# mixer-board1.net
KiCad netlist of a schematic drawn in EAGLE
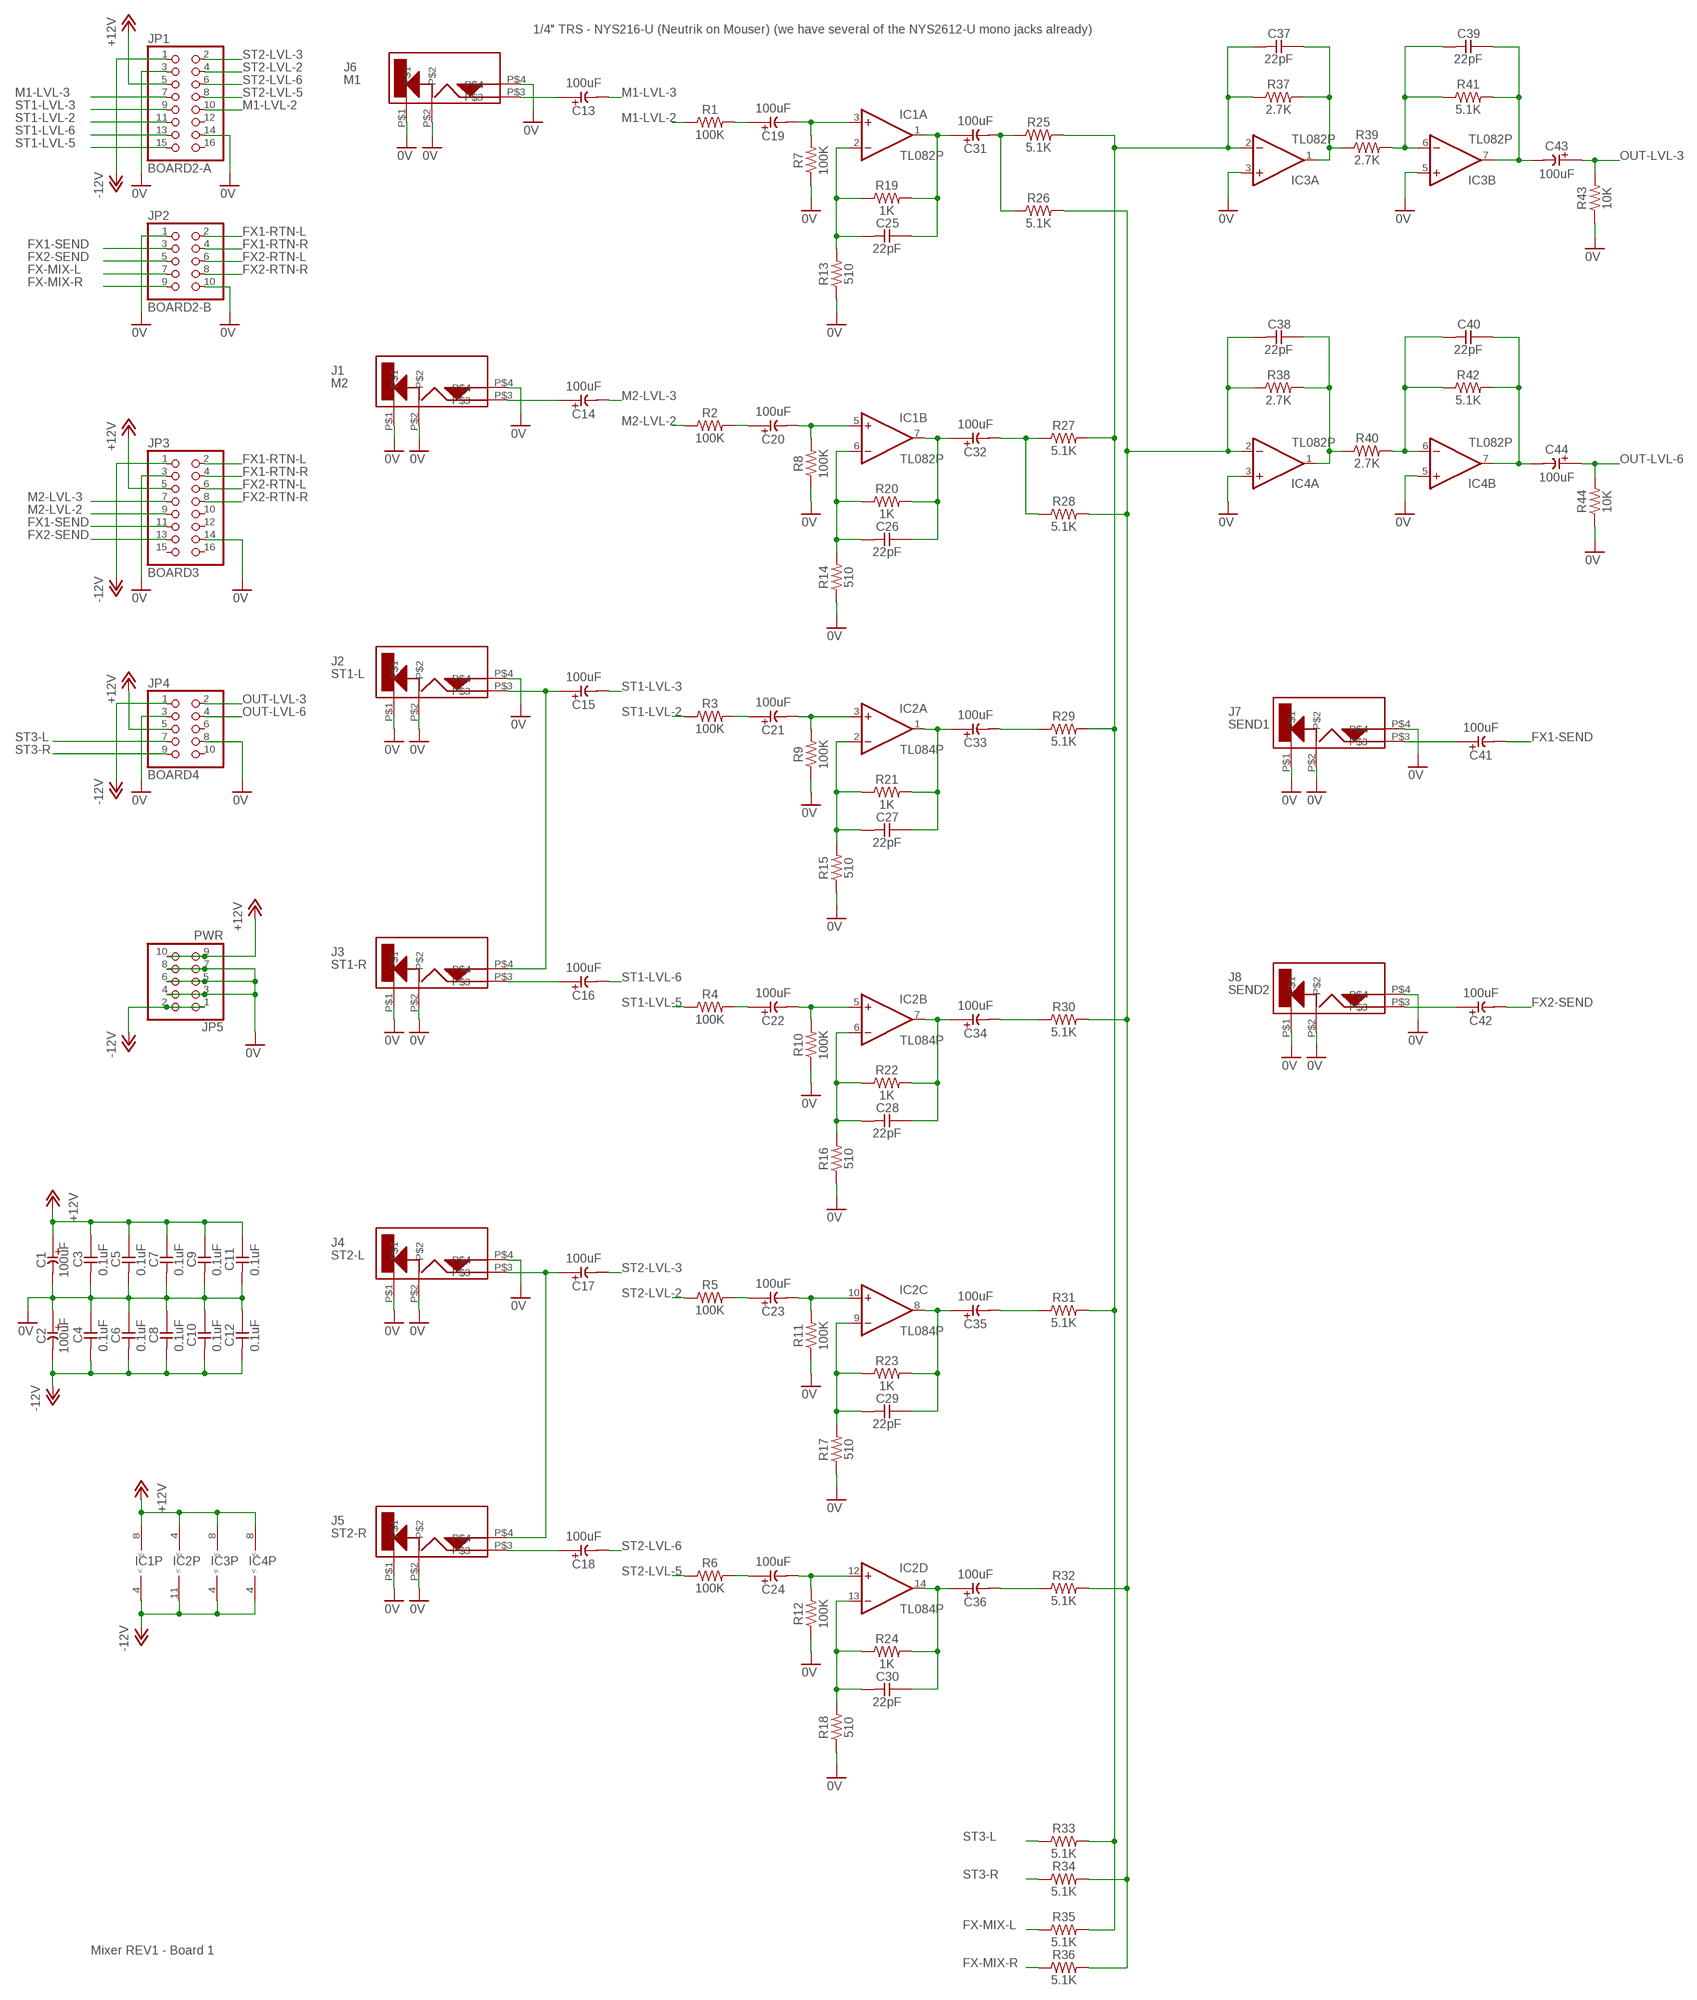
[diagram p0: schematic, sheet 1]

(export (version "E")
  (design (tool "Eeschema 10.0.6"))
  (components
    (comp (ref "C1")
      (value "100uF")
      (footprint "eagle-import:E5-8,5")
      (libsource (lib "eagle-import") (part "CE-USE5-8.5"))
    )
    (comp (ref "C2")
      (value "100uF")
      (footprint "eagle-import:E5-8,5")
      (libsource (lib "eagle-import") (part "CE-USE5-8.5"))
    )
    (comp (ref "C3")
      (value "0.1uF")
      (footprint "eagle-import:C025-024X044")
      (libsource (lib "eagle-import") (part "_common.v1_CC-US025-024X044"))
    )
    (comp (ref "C4")
      (value "0.1uF")
      (footprint "eagle-import:C025-024X044")
      (libsource (lib "eagle-import") (part "_common.v1_CC-US025-024X044"))
    )
    (comp (ref "C5")
      (value "0.1uF")
      (footprint "eagle-import:C025-024X044")
      (libsource (lib "eagle-import") (part "_common.v1_CC-US025-024X044"))
    )
    (comp (ref "C6")
      (value "0.1uF")
      (footprint "eagle-import:C025-024X044")
      (libsource (lib "eagle-import") (part "_common.v1_CC-US025-024X044"))
    )
    (comp (ref "C7")
      (value "0.1uF")
      (footprint "eagle-import:C025-024X044")
      (libsource (lib "eagle-import") (part "_common.v1_CC-US025-024X044"))
    )
    (comp (ref "C8")
      (value "0.1uF")
      (footprint "eagle-import:C025-024X044")
      (libsource (lib "eagle-import") (part "_common.v1_CC-US025-024X044"))
    )
    (comp (ref "C9")
      (value "0.1uF")
      (footprint "eagle-import:C025-024X044")
      (libsource (lib "eagle-import") (part "_common.v1_CC-US025-024X044"))
    )
    (comp (ref "C10")
      (value "0.1uF")
      (footprint "eagle-import:C025-024X044")
      (libsource (lib "eagle-import") (part "_common.v1_CC-US025-024X044"))
    )
    (comp (ref "C11")
      (value "0.1uF")
      (footprint "eagle-import:C025-024X044")
      (libsource (lib "eagle-import") (part "_common.v1_CC-US025-024X044"))
    )
    (comp (ref "C12")
      (value "0.1uF")
      (footprint "eagle-import:C025-024X044")
      (libsource (lib "eagle-import") (part "_common.v1_CC-US025-024X044"))
    )
    (comp (ref "C13")
      (value "100uF")
      (footprint "eagle-import:E5-8,5")
      (libsource (lib "eagle-import") (part "CE-USE5-8.5"))
    )
    (comp (ref "C14")
      (value "100uF")
      (footprint "eagle-import:E5-8,5")
      (libsource (lib "eagle-import") (part "CE-USE5-8.5"))
    )
    (comp (ref "C15")
      (value "100uF")
      (footprint "eagle-import:E5-8,5")
      (libsource (lib "eagle-import") (part "CE-USE5-8.5"))
    )
    (comp (ref "C16")
      (value "100uF")
      (footprint "eagle-import:E5-8,5")
      (libsource (lib "eagle-import") (part "CE-USE5-8.5"))
    )
    (comp (ref "C17")
      (value "100uF")
      (footprint "eagle-import:E5-8,5")
      (libsource (lib "eagle-import") (part "CE-USE5-8.5"))
    )
    (comp (ref "C18")
      (value "100uF")
      (footprint "eagle-import:E5-8,5")
      (libsource (lib "eagle-import") (part "CE-USE5-8.5"))
    )
    (comp (ref "C19")
      (value "100uF")
      (footprint "eagle-import:E5-8,5")
      (libsource (lib "eagle-import") (part "CE-USE5-8.5"))
    )
    (comp (ref "C20")
      (value "100uF")
      (footprint "eagle-import:E5-8,5")
      (libsource (lib "eagle-import") (part "CE-USE5-8.5"))
    )
    (comp (ref "C21")
      (value "100uF")
      (footprint "eagle-import:E5-8,5")
      (libsource (lib "eagle-import") (part "CE-USE5-8.5"))
    )
    (comp (ref "C22")
      (value "100uF")
      (footprint "eagle-import:E5-8,5")
      (libsource (lib "eagle-import") (part "CE-USE5-8.5"))
    )
    (comp (ref "C23")
      (value "100uF")
      (footprint "eagle-import:E5-8,5")
      (libsource (lib "eagle-import") (part "CE-USE5-8.5"))
    )
    (comp (ref "C24")
      (value "100uF")
      (footprint "eagle-import:E5-8,5")
      (libsource (lib "eagle-import") (part "CE-USE5-8.5"))
    )
    (comp (ref "C25")
      (value "22pF")
      (footprint "eagle-import:C025-024X044")
      (libsource (lib "eagle-import") (part "CC-US025-024X044"))
    )
    (comp (ref "C26")
      (value "22pF")
      (footprint "eagle-import:C025-024X044")
      (libsource (lib "eagle-import") (part "CC-US025-024X044"))
    )
    (comp (ref "C27")
      (value "22pF")
      (footprint "eagle-import:C025-024X044")
      (libsource (lib "eagle-import") (part "CC-US025-024X044"))
    )
    (comp (ref "C28")
      (value "22pF")
      (footprint "eagle-import:C025-024X044")
      (libsource (lib "eagle-import") (part "CC-US025-024X044"))
    )
    (comp (ref "C29")
      (value "22pF")
      (footprint "eagle-import:C025-024X044")
      (libsource (lib "eagle-import") (part "CC-US025-024X044"))
    )
    (comp (ref "C30")
      (value "22pF")
      (footprint "eagle-import:C025-024X044")
      (libsource (lib "eagle-import") (part "CC-US025-024X044"))
    )
    (comp (ref "C31")
      (value "100uF")
      (footprint "eagle-import:E5-8,5")
      (libsource (lib "eagle-import") (part "CE-USE5-8.5"))
    )
    (comp (ref "C32")
      (value "100uF")
      (footprint "eagle-import:E5-8,5")
      (libsource (lib "eagle-import") (part "CE-USE5-8.5"))
    )
    (comp (ref "C33")
      (value "100uF")
      (footprint "eagle-import:E5-8,5")
      (libsource (lib "eagle-import") (part "CE-USE5-8.5"))
    )
    (comp (ref "C34")
      (value "100uF")
      (footprint "eagle-import:E5-8,5")
      (libsource (lib "eagle-import") (part "CE-USE5-8.5"))
    )
    (comp (ref "C35")
      (value "100uF")
      (footprint "eagle-import:E5-8,5")
      (libsource (lib "eagle-import") (part "CE-USE5-8.5"))
    )
    (comp (ref "C36")
      (value "100uF")
      (footprint "eagle-import:E5-8,5")
      (libsource (lib "eagle-import") (part "CE-USE5-8.5"))
    )
    (comp (ref "C37")
      (value "22pF")
      (footprint "eagle-import:C025-024X044")
      (libsource (lib "eagle-import") (part "CC-US025-024X044"))
    )
    (comp (ref "C38")
      (value "22pF")
      (footprint "eagle-import:C025-024X044")
      (libsource (lib "eagle-import") (part "CC-US025-024X044"))
    )
    (comp (ref "C39")
      (value "22pF")
      (footprint "eagle-import:C025-024X044")
      (libsource (lib "eagle-import") (part "CC-US025-024X044"))
    )
    (comp (ref "C40")
      (value "22pF")
      (footprint "eagle-import:C025-024X044")
      (libsource (lib "eagle-import") (part "CC-US025-024X044"))
    )
    (comp (ref "C41")
      (value "100uF")
      (footprint "eagle-import:E5-8,5")
      (libsource (lib "eagle-import") (part "CE-USE5-8.5"))
    )
    (comp (ref "C42")
      (value "100uF")
      (footprint "eagle-import:E5-8,5")
      (libsource (lib "eagle-import") (part "CE-USE5-8.5"))
    )
    (comp (ref "C43")
      (value "100uF")
      (footprint "eagle-import:E5-8,5")
      (libsource (lib "eagle-import") (part "CE-USE5-8.5"))
    )
    (comp (ref "C44")
      (value "100uF")
      (footprint "eagle-import:E5-8,5")
      (libsource (lib "eagle-import") (part "CE-USE5-8.5"))
    )
    (comp (ref "IC1")
      (value "TL082P")
      (footprint "eagle-import:DIL08")
      (libsource (lib "eagle-import") (part "TL082P"))
    )
    (comp (ref "IC2")
      (value "TL084P")
      (footprint "eagle-import:DIL14")
      (libsource (lib "eagle-import") (part "TL084P"))
    )
    (comp (ref "IC3")
      (value "TL082P")
      (footprint "eagle-import:DIL08")
      (libsource (lib "eagle-import") (part "TL082P"))
    )
    (comp (ref "IC4")
      (value "TL082P")
      (footprint "eagle-import:DIL08")
      (libsource (lib "eagle-import") (part "TL082P"))
    )
    (comp (ref "J1")
      (value "M2")
      (footprint "eagle-import:CL1384")
      (libsource (lib "eagle-import") (part "CL1384"))
    )
    (comp (ref "J2")
      (value "ST1-L")
      (footprint "eagle-import:CL1384")
      (libsource (lib "eagle-import") (part "CL1384"))
    )
    (comp (ref "J3")
      (value "ST1-R")
      (footprint "eagle-import:CL1384")
      (libsource (lib "eagle-import") (part "CL1384"))
    )
    (comp (ref "J4")
      (value "ST2-L")
      (footprint "eagle-import:CL1384")
      (libsource (lib "eagle-import") (part "CL1384"))
    )
    (comp (ref "J5")
      (value "ST2-R")
      (footprint "eagle-import:CL1384")
      (libsource (lib "eagle-import") (part "CL1384"))
    )
    (comp (ref "J6")
      (value "M1")
      (footprint "eagle-import:CL1384")
      (libsource (lib "eagle-import") (part "CL1384"))
    )
    (comp (ref "J7")
      (value "SEND1")
      (footprint "eagle-import:CL1384")
      (libsource (lib "eagle-import") (part "CL1384"))
    )
    (comp (ref "J8")
      (value "SEND2")
      (footprint "eagle-import:CL1384")
      (libsource (lib "eagle-import") (part "CL1384"))
    )
    (comp (ref "JP1")
      (value "BOARD2-A")
      (footprint "eagle-import:2X08")
      (libsource (lib "eagle-import") (part "PINHD-2X8"))
    )
    (comp (ref "JP2")
      (value "BOARD2-B")
      (footprint "eagle-import:2X05")
      (libsource (lib "eagle-import") (part "PINHD-2X5"))
    )
    (comp (ref "JP3")
      (value "BOARD3")
      (footprint "eagle-import:2X08")
      (libsource (lib "eagle-import") (part "PINHD-2X8"))
    )
    (comp (ref "JP4")
      (value "BOARD4")
      (footprint "eagle-import:2X05")
      (libsource (lib "eagle-import") (part "PINHD-2X5"))
    )
    (comp (ref "JP5")
      (value "PWR")
      (footprint "eagle-import:2X05")
      (libsource (lib "eagle-import") (part "PINHD-2X5"))
    )
    (comp (ref "R1")
      (value "100K")
      (footprint "eagle-import:0207_7")
      (libsource (lib "eagle-import") (part "R"))
    )
    (comp (ref "R2")
      (value "100K")
      (footprint "eagle-import:0207_7")
      (libsource (lib "eagle-import") (part "R"))
    )
    (comp (ref "R3")
      (value "100K")
      (footprint "eagle-import:0207_7")
      (libsource (lib "eagle-import") (part "R"))
    )
    (comp (ref "R4")
      (value "100K")
      (footprint "eagle-import:0207_7")
      (libsource (lib "eagle-import") (part "R"))
    )
    (comp (ref "R5")
      (value "100K")
      (footprint "eagle-import:0207_7")
      (libsource (lib "eagle-import") (part "R"))
    )
    (comp (ref "R6")
      (value "100K")
      (footprint "eagle-import:0207_7")
      (libsource (lib "eagle-import") (part "R"))
    )
    (comp (ref "R7")
      (value "100K")
      (footprint "eagle-import:0207_7")
      (libsource (lib "eagle-import") (part "R"))
    )
    (comp (ref "R8")
      (value "100K")
      (footprint "eagle-import:0207_7")
      (libsource (lib "eagle-import") (part "R"))
    )
    (comp (ref "R9")
      (value "100K")
      (footprint "eagle-import:0207_7")
      (libsource (lib "eagle-import") (part "R"))
    )
    (comp (ref "R10")
      (value "100K")
      (footprint "eagle-import:0207_7")
      (libsource (lib "eagle-import") (part "R"))
    )
    (comp (ref "R11")
      (value "100K")
      (footprint "eagle-import:0207_7")
      (libsource (lib "eagle-import") (part "R"))
    )
    (comp (ref "R12")
      (value "100K")
      (footprint "eagle-import:0207_7")
      (libsource (lib "eagle-import") (part "R"))
    )
    (comp (ref "R13")
      (value "510")
      (footprint "eagle-import:0207_7")
      (libsource (lib "eagle-import") (part "R"))
    )
    (comp (ref "R14")
      (value "510")
      (footprint "eagle-import:0207_7")
      (libsource (lib "eagle-import") (part "R"))
    )
    (comp (ref "R15")
      (value "510")
      (footprint "eagle-import:0207_7")
      (libsource (lib "eagle-import") (part "R"))
    )
    (comp (ref "R16")
      (value "510")
      (footprint "eagle-import:0207_7")
      (libsource (lib "eagle-import") (part "R"))
    )
    (comp (ref "R17")
      (value "510")
      (footprint "eagle-import:0207_7")
      (libsource (lib "eagle-import") (part "R"))
    )
    (comp (ref "R18")
      (value "510")
      (footprint "eagle-import:0207_7")
      (libsource (lib "eagle-import") (part "R"))
    )
    (comp (ref "R19")
      (value "1K")
      (footprint "eagle-import:0207_7")
      (libsource (lib "eagle-import") (part "R"))
    )
    (comp (ref "R20")
      (value "1K")
      (footprint "eagle-import:0207_7")
      (libsource (lib "eagle-import") (part "R"))
    )
    (comp (ref "R21")
      (value "1K")
      (footprint "eagle-import:0207_7")
      (libsource (lib "eagle-import") (part "R"))
    )
    (comp (ref "R22")
      (value "1K")
      (footprint "eagle-import:0207_7")
      (libsource (lib "eagle-import") (part "R"))
    )
    (comp (ref "R23")
      (value "1K")
      (footprint "eagle-import:0207_7")
      (libsource (lib "eagle-import") (part "R"))
    )
    (comp (ref "R24")
      (value "1K")
      (footprint "eagle-import:0207_7")
      (libsource (lib "eagle-import") (part "R"))
    )
    (comp (ref "R25")
      (value "5.1K")
      (footprint "eagle-import:0207_7")
      (libsource (lib "eagle-import") (part "R"))
    )
    (comp (ref "R26")
      (value "5.1K")
      (footprint "eagle-import:0207_7")
      (libsource (lib "eagle-import") (part "R"))
    )
    (comp (ref "R27")
      (value "5.1K")
      (footprint "eagle-import:0207_7")
      (libsource (lib "eagle-import") (part "R"))
    )
    (comp (ref "R28")
      (value "5.1K")
      (footprint "eagle-import:0207_7")
      (libsource (lib "eagle-import") (part "R"))
    )
    (comp (ref "R29")
      (value "5.1K")
      (footprint "eagle-import:0207_7")
      (libsource (lib "eagle-import") (part "R"))
    )
    (comp (ref "R30")
      (value "5.1K")
      (footprint "eagle-import:0207_7")
      (libsource (lib "eagle-import") (part "R"))
    )
    (comp (ref "R31")
      (value "5.1K")
      (footprint "eagle-import:0207_7")
      (libsource (lib "eagle-import") (part "R"))
    )
    (comp (ref "R32")
      (value "5.1K")
      (footprint "eagle-import:0207_7")
      (libsource (lib "eagle-import") (part "R"))
    )
    (comp (ref "R33")
      (value "5.1K")
      (footprint "eagle-import:0207_7")
      (libsource (lib "eagle-import") (part "R"))
    )
    (comp (ref "R34")
      (value "5.1K")
      (footprint "eagle-import:0207_7")
      (libsource (lib "eagle-import") (part "R"))
    )
    (comp (ref "R35")
      (value "5.1K")
      (footprint "eagle-import:0207_7")
      (libsource (lib "eagle-import") (part "R"))
    )
    (comp (ref "R36")
      (value "5.1K")
      (footprint "eagle-import:0207_7")
      (libsource (lib "eagle-import") (part "R"))
    )
    (comp (ref "R37")
      (value "2.7K")
      (footprint "eagle-import:0207_7")
      (libsource (lib "eagle-import") (part "R"))
    )
    (comp (ref "R38")
      (value "2.7K")
      (footprint "eagle-import:0207_7")
      (libsource (lib "eagle-import") (part "R"))
    )
    (comp (ref "R39")
      (value "2.7K")
      (footprint "eagle-import:0207_7")
      (libsource (lib "eagle-import") (part "R"))
    )
    (comp (ref "R40")
      (value "2.7K")
      (footprint "eagle-import:0207_7")
      (libsource (lib "eagle-import") (part "R"))
    )
    (comp (ref "R41")
      (value "5.1K")
      (footprint "eagle-import:0207_7")
      (libsource (lib "eagle-import") (part "R"))
    )
    (comp (ref "R42")
      (value "5.1K")
      (footprint "eagle-import:0207_7")
      (libsource (lib "eagle-import") (part "R"))
    )
    (comp (ref "R43")
      (value "10K")
      (footprint "eagle-import:0207_7")
      (libsource (lib "eagle-import") (part "R"))
    )
    (comp (ref "R44")
      (value "10K")
      (footprint "eagle-import:0207_7")
      (libsource (lib "eagle-import") (part "R"))
    )
  )
  (nets
    (net (code "1") (name "+12V") (class "Default")
      (node (ref "C1") (pin "+") (pinfunction "+_+") (pintype "passive"))
      (node (ref "C11") (pin "1") (pinfunction "1_1") (pintype "passive"))
      (node (ref "C3") (pin "1") (pinfunction "1_1") (pintype "passive"))
      (node (ref "C5") (pin "1") (pinfunction "1_1") (pintype "passive"))
      (node (ref "C7") (pin "1") (pinfunction "1_1") (pintype "passive"))
      (node (ref "C9") (pin "1") (pinfunction "1_1") (pintype "passive"))
      (node (ref "IC1") (pin "8") (pinfunction "V+_8") (pintype "power_in"))
      (node (ref "IC2") (pin "4") (pinfunction "V+_4") (pintype "power_in"))
      (node (ref "IC3") (pin "8") (pinfunction "V+_8") (pintype "power_in"))
      (node (ref "IC4") (pin "8") (pinfunction "V+_8") (pintype "power_in"))
      (node (ref "JP1") (pin "5") (pinfunction "5_5") (pintype "passive"))
      (node (ref "JP3") (pin "5") (pinfunction "5_5") (pintype "passive"))
      (node (ref "JP4") (pin "5") (pinfunction "5_5") (pintype "passive"))
      (node (ref "JP5") (pin "10") (pinfunction "10_10") (pintype "passive"))
      (node (ref "JP5") (pin "9") (pinfunction "9_9") (pintype "passive"))
    )
    (net (code "2") (name "-12V") (class "Default")
      (node (ref "C10") (pin "2") (pinfunction "2_2") (pintype "passive"))
      (node (ref "C12") (pin "2") (pinfunction "2_2") (pintype "passive"))
      (node (ref "C2") (pin "-") (pinfunction "-_-") (pintype "passive"))
      (node (ref "C4") (pin "2") (pinfunction "2_2") (pintype "passive"))
      (node (ref "C6") (pin "2") (pinfunction "2_2") (pintype "passive"))
      (node (ref "C8") (pin "2") (pinfunction "2_2") (pintype "passive"))
      (node (ref "IC1") (pin "4") (pinfunction "V-_4") (pintype "power_in"))
      (node (ref "IC2") (pin "11") (pinfunction "V-_11") (pintype "power_in"))
      (node (ref "IC3") (pin "4") (pinfunction "V-_4") (pintype "power_in"))
      (node (ref "IC4") (pin "4") (pinfunction "V-_4") (pintype "power_in"))
      (node (ref "JP1") (pin "1") (pinfunction "1_1") (pintype "passive"))
      (node (ref "JP3") (pin "1") (pinfunction "1_1") (pintype "passive"))
      (node (ref "JP4") (pin "1") (pinfunction "1_1") (pintype "passive"))
      (node (ref "JP5") (pin "1") (pinfunction "1_1") (pintype "passive"))
      (node (ref "JP5") (pin "2") (pinfunction "2_2") (pintype "passive"))
    )
    (net (code "3") (name "/FX-MIX-L") (class "Default")
      (node (ref "JP2") (pin "7") (pinfunction "7_7") (pintype "passive"))
      (node (ref "R35") (pin "1") (pinfunction "1_1") (pintype "passive"))
    )
    (net (code "4") (name "/FX-MIX-R") (class "Default")
      (node (ref "JP2") (pin "9") (pinfunction "9_9") (pintype "passive"))
      (node (ref "R36") (pin "1") (pinfunction "1_1") (pintype "passive"))
    )
    (net (code "5") (name "/FX1-RTN-L") (class "Default")
      (node (ref "JP2") (pin "2") (pinfunction "2_2") (pintype "passive"))
      (node (ref "JP3") (pin "2") (pinfunction "2_2") (pintype "passive"))
    )
    (net (code "6") (name "/FX1-RTN-R") (class "Default")
      (node (ref "JP2") (pin "4") (pinfunction "4_4") (pintype "passive"))
      (node (ref "JP3") (pin "4") (pinfunction "4_4") (pintype "passive"))
    )
    (net (code "7") (name "/FX1-SEND") (class "Default")
      (node (ref "C41") (pin "-") (pinfunction "-_-") (pintype "passive"))
      (node (ref "JP2") (pin "3") (pinfunction "3_3") (pintype "passive"))
      (node (ref "JP3") (pin "11") (pinfunction "11_11") (pintype "passive"))
    )
    (net (code "8") (name "/FX2-RTN-L") (class "Default")
      (node (ref "JP2") (pin "6") (pinfunction "6_6") (pintype "passive"))
      (node (ref "JP3") (pin "6") (pinfunction "6_6") (pintype "passive"))
    )
    (net (code "9") (name "/FX2-RTN-R") (class "Default")
      (node (ref "JP2") (pin "8") (pinfunction "8_8") (pintype "passive"))
      (node (ref "JP3") (pin "8") (pinfunction "8_8") (pintype "passive"))
    )
    (net (code "10") (name "/FX2-SEND") (class "Default")
      (node (ref "C42") (pin "-") (pinfunction "-_-") (pintype "passive"))
      (node (ref "JP2") (pin "5") (pinfunction "5_5") (pintype "passive"))
      (node (ref "JP3") (pin "13") (pinfunction "13_13") (pintype "passive"))
    )
    (net (code "11") (name "/M1-LVL-2") (class "Default")
      (node (ref "JP1") (pin "10") (pinfunction "10_10") (pintype "passive"))
      (node (ref "R1") (pin "1") (pinfunction "1_1") (pintype "passive"))
    )
    (net (code "12") (name "/M1-LVL-3") (class "Default")
      (node (ref "C13") (pin "-") (pinfunction "-_-") (pintype "passive"))
      (node (ref "JP1") (pin "7") (pinfunction "7_7") (pintype "passive"))
    )
    (net (code "13") (name "/M2-LVL-2") (class "Default")
      (node (ref "JP3") (pin "9") (pinfunction "9_9") (pintype "passive"))
      (node (ref "R2") (pin "1") (pinfunction "1_1") (pintype "passive"))
    )
    (net (code "14") (name "/M2-LVL-3") (class "Default")
      (node (ref "C14") (pin "-") (pinfunction "-_-") (pintype "passive"))
      (node (ref "JP3") (pin "7") (pinfunction "7_7") (pintype "passive"))
    )
    (net (code "15") (name "/OUT-LVL-3") (class "Default")
      (node (ref "C43") (pin "+") (pinfunction "+_+") (pintype "passive"))
      (node (ref "JP4") (pin "2") (pinfunction "2_2") (pintype "passive"))
      (node (ref "R43") (pin "2") (pinfunction "2_2") (pintype "passive"))
    )
    (net (code "16") (name "/OUT-LVL-6") (class "Default")
      (node (ref "C44") (pin "+") (pinfunction "+_+") (pintype "passive"))
      (node (ref "JP4") (pin "4") (pinfunction "4_4") (pintype "passive"))
      (node (ref "R44") (pin "2") (pinfunction "2_2") (pintype "passive"))
    )
    (net (code "17") (name "/ST1-LVL-2") (class "Default")
      (node (ref "JP1") (pin "11") (pinfunction "11_11") (pintype "passive"))
      (node (ref "R3") (pin "1") (pinfunction "1_1") (pintype "passive"))
    )
    (net (code "18") (name "/ST1-LVL-3") (class "Default")
      (node (ref "C15") (pin "-") (pinfunction "-_-") (pintype "passive"))
      (node (ref "JP1") (pin "9") (pinfunction "9_9") (pintype "passive"))
    )
    (net (code "19") (name "/ST1-LVL-5") (class "Default")
      (node (ref "JP1") (pin "15") (pinfunction "15_15") (pintype "passive"))
      (node (ref "R4") (pin "1") (pinfunction "1_1") (pintype "passive"))
    )
    (net (code "20") (name "/ST1-LVL-6") (class "Default")
      (node (ref "C16") (pin "-") (pinfunction "-_-") (pintype "passive"))
      (node (ref "JP1") (pin "13") (pinfunction "13_13") (pintype "passive"))
    )
    (net (code "21") (name "/ST2-LVL-2") (class "Default")
      (node (ref "JP1") (pin "4") (pinfunction "4_4") (pintype "passive"))
      (node (ref "R5") (pin "1") (pinfunction "1_1") (pintype "passive"))
    )
    (net (code "22") (name "/ST2-LVL-3") (class "Default")
      (node (ref "C17") (pin "-") (pinfunction "-_-") (pintype "passive"))
      (node (ref "JP1") (pin "2") (pinfunction "2_2") (pintype "passive"))
    )
    (net (code "23") (name "/ST2-LVL-5") (class "Default")
      (node (ref "JP1") (pin "8") (pinfunction "8_8") (pintype "passive"))
      (node (ref "R6") (pin "1") (pinfunction "1_1") (pintype "passive"))
    )
    (net (code "24") (name "/ST2-LVL-6") (class "Default")
      (node (ref "C18") (pin "-") (pinfunction "-_-") (pintype "passive"))
      (node (ref "JP1") (pin "6") (pinfunction "6_6") (pintype "passive"))
    )
    (net (code "25") (name "/ST3-L") (class "Default")
      (node (ref "JP4") (pin "7") (pinfunction "7_7") (pintype "passive"))
      (node (ref "R33") (pin "1") (pinfunction "1_1") (pintype "passive"))
    )
    (net (code "26") (name "/ST3-R") (class "Default")
      (node (ref "JP4") (pin "9") (pinfunction "9_9") (pintype "passive"))
      (node (ref "R34") (pin "1") (pinfunction "1_1") (pintype "passive"))
    )
    (net (code "27") (name "0V") (class "Default")
      (node (ref "C1") (pin "-") (pinfunction "-_-") (pintype "passive"))
      (node (ref "C10") (pin "1") (pinfunction "1_1") (pintype "passive"))
      (node (ref "C11") (pin "2") (pinfunction "2_2") (pintype "passive"))
      (node (ref "C12") (pin "1") (pinfunction "1_1") (pintype "passive"))
      (node (ref "C2") (pin "+") (pinfunction "+_+") (pintype "passive"))
      (node (ref "C3") (pin "2") (pinfunction "2_2") (pintype "passive"))
      (node (ref "C4") (pin "1") (pinfunction "1_1") (pintype "passive"))
      (node (ref "C5") (pin "2") (pinfunction "2_2") (pintype "passive"))
      (node (ref "C6") (pin "1") (pinfunction "1_1") (pintype "passive"))
      (node (ref "C7") (pin "2") (pinfunction "2_2") (pintype "passive"))
      (node (ref "C8") (pin "1") (pinfunction "1_1") (pintype "passive"))
      (node (ref "C9") (pin "2") (pinfunction "2_2") (pintype "passive"))
      (node (ref "IC3") (pin "3") (pinfunction "+IN_3") (pintype "input"))
      (node (ref "IC3") (pin "5") (pinfunction "+IN_5") (pintype "input"))
      (node (ref "IC4") (pin "3") (pinfunction "+IN_3") (pintype "input"))
      (node (ref "IC4") (pin "5") (pinfunction "+IN_5") (pintype "input"))
      (node (ref "J1") (pin "P$1") (pinfunction "P$1_P$1") (pintype "bidirectional"))
      (node (ref "J1") (pin "P$2") (pinfunction "P$2_P$2") (pintype "bidirectional"))
      (node (ref "J1") (pin "P$4") (pinfunction "P$4_P$4") (pintype "bidirectional"))
      (node (ref "J2") (pin "P$1") (pinfunction "P$1_P$1") (pintype "bidirectional"))
      (node (ref "J2") (pin "P$2") (pinfunction "P$2_P$2") (pintype "bidirectional"))
      (node (ref "J2") (pin "P$4") (pinfunction "P$4_P$4") (pintype "bidirectional"))
      (node (ref "J3") (pin "P$1") (pinfunction "P$1_P$1") (pintype "bidirectional"))
      (node (ref "J3") (pin "P$2") (pinfunction "P$2_P$2") (pintype "bidirectional"))
      (node (ref "J4") (pin "P$1") (pinfunction "P$1_P$1") (pintype "bidirectional"))
      (node (ref "J4") (pin "P$2") (pinfunction "P$2_P$2") (pintype "bidirectional"))
      (node (ref "J4") (pin "P$4") (pinfunction "P$4_P$4") (pintype "bidirectional"))
      (node (ref "J5") (pin "P$1") (pinfunction "P$1_P$1") (pintype "bidirectional"))
      (node (ref "J5") (pin "P$2") (pinfunction "P$2_P$2") (pintype "bidirectional"))
      (node (ref "J6") (pin "P$1") (pinfunction "P$1_P$1") (pintype "bidirectional"))
      (node (ref "J6") (pin "P$2") (pinfunction "P$2_P$2") (pintype "bidirectional"))
      (node (ref "J6") (pin "P$4") (pinfunction "P$4_P$4") (pintype "bidirectional"))
      (node (ref "J7") (pin "P$1") (pinfunction "P$1_P$1") (pintype "bidirectional"))
      (node (ref "J7") (pin "P$2") (pinfunction "P$2_P$2") (pintype "bidirectional"))
      (node (ref "J7") (pin "P$4") (pinfunction "P$4_P$4") (pintype "bidirectional"))
      (node (ref "J8") (pin "P$1") (pinfunction "P$1_P$1") (pintype "bidirectional"))
      (node (ref "J8") (pin "P$2") (pinfunction "P$2_P$2") (pintype "bidirectional"))
      (node (ref "J8") (pin "P$4") (pinfunction "P$4_P$4") (pintype "bidirectional"))
      (node (ref "JP1") (pin "14") (pinfunction "14_14") (pintype "passive"))
      (node (ref "JP1") (pin "3") (pinfunction "3_3") (pintype "passive"))
      (node (ref "JP2") (pin "1") (pinfunction "1_1") (pintype "passive"))
      (node (ref "JP2") (pin "10") (pinfunction "10_10") (pintype "passive"))
      (node (ref "JP3") (pin "14") (pinfunction "14_14") (pintype "passive"))
      (node (ref "JP3") (pin "3") (pinfunction "3_3") (pintype "passive"))
      (node (ref "JP4") (pin "3") (pinfunction "3_3") (pintype "passive"))
      (node (ref "JP4") (pin "8") (pinfunction "8_8") (pintype "passive"))
      (node (ref "JP5") (pin "3") (pinfunction "3_3") (pintype "passive"))
      (node (ref "JP5") (pin "4") (pinfunction "4_4") (pintype "passive"))
      (node (ref "JP5") (pin "5") (pinfunction "5_5") (pintype "passive"))
      (node (ref "JP5") (pin "6") (pinfunction "6_6") (pintype "passive"))
      (node (ref "JP5") (pin "7") (pinfunction "7_7") (pintype "passive"))
      (node (ref "JP5") (pin "8") (pinfunction "8_8") (pintype "passive"))
      (node (ref "R10") (pin "1") (pinfunction "1_1") (pintype "passive"))
      (node (ref "R11") (pin "1") (pinfunction "1_1") (pintype "passive"))
      (node (ref "R12") (pin "1") (pinfunction "1_1") (pintype "passive"))
      (node (ref "R13") (pin "1") (pinfunction "1_1") (pintype "passive"))
      (node (ref "R14") (pin "1") (pinfunction "1_1") (pintype "passive"))
      (node (ref "R15") (pin "1") (pinfunction "1_1") (pintype "passive"))
      (node (ref "R16") (pin "1") (pinfunction "1_1") (pintype "passive"))
      (node (ref "R17") (pin "1") (pinfunction "1_1") (pintype "passive"))
      (node (ref "R18") (pin "1") (pinfunction "1_1") (pintype "passive"))
      (node (ref "R43") (pin "1") (pinfunction "1_1") (pintype "passive"))
      (node (ref "R44") (pin "1") (pinfunction "1_1") (pintype "passive"))
      (node (ref "R7") (pin "1") (pinfunction "1_1") (pintype "passive"))
      (node (ref "R8") (pin "1") (pinfunction "1_1") (pintype "passive"))
      (node (ref "R9") (pin "1") (pinfunction "1_1") (pintype "passive"))
    )
    (net (code "28") (name "Net-(C13-Pad+)") (class "Default")
      (node (ref "C13") (pin "+") (pinfunction "+_+") (pintype "passive"))
      (node (ref "J6") (pin "P$3") (pinfunction "P$3_P$3") (pintype "bidirectional"))
    )
    (net (code "29") (name "Net-(C14-Pad+)") (class "Default")
      (node (ref "C14") (pin "+") (pinfunction "+_+") (pintype "passive"))
      (node (ref "J1") (pin "P$3") (pinfunction "P$3_P$3") (pintype "bidirectional"))
    )
    (net (code "30") (name "Net-(C15-Pad+)") (class "Default")
      (node (ref "C15") (pin "+") (pinfunction "+_+") (pintype "passive"))
      (node (ref "J2") (pin "P$3") (pinfunction "P$3_P$3") (pintype "bidirectional"))
      (node (ref "J3") (pin "P$4") (pinfunction "P$4_P$4") (pintype "bidirectional"))
    )
    (net (code "31") (name "Net-(C16-Pad+)") (class "Default")
      (node (ref "C16") (pin "+") (pinfunction "+_+") (pintype "passive"))
      (node (ref "J3") (pin "P$3") (pinfunction "P$3_P$3") (pintype "bidirectional"))
    )
    (net (code "32") (name "Net-(C17-Pad+)") (class "Default")
      (node (ref "C17") (pin "+") (pinfunction "+_+") (pintype "passive"))
      (node (ref "J4") (pin "P$3") (pinfunction "P$3_P$3") (pintype "bidirectional"))
      (node (ref "J5") (pin "P$4") (pinfunction "P$4_P$4") (pintype "bidirectional"))
    )
    (net (code "33") (name "Net-(C18-Pad+)") (class "Default")
      (node (ref "C18") (pin "+") (pinfunction "+_+") (pintype "passive"))
      (node (ref "J5") (pin "P$3") (pinfunction "P$3_P$3") (pintype "bidirectional"))
    )
    (net (code "34") (name "Net-(C19-Pad+)") (class "Default")
      (node (ref "C19") (pin "+") (pinfunction "+_+") (pintype "passive"))
      (node (ref "R1") (pin "2") (pinfunction "2_2") (pintype "passive"))
    )
    (net (code "35") (name "Net-(C20-Pad+)") (class "Default")
      (node (ref "C20") (pin "+") (pinfunction "+_+") (pintype "passive"))
      (node (ref "R2") (pin "2") (pinfunction "2_2") (pintype "passive"))
    )
    (net (code "36") (name "Net-(C21-Pad+)") (class "Default")
      (node (ref "C21") (pin "+") (pinfunction "+_+") (pintype "passive"))
      (node (ref "R3") (pin "2") (pinfunction "2_2") (pintype "passive"))
    )
    (net (code "37") (name "Net-(C22-Pad+)") (class "Default")
      (node (ref "C22") (pin "+") (pinfunction "+_+") (pintype "passive"))
      (node (ref "R4") (pin "2") (pinfunction "2_2") (pintype "passive"))
    )
    (net (code "38") (name "Net-(C23-Pad+)") (class "Default")
      (node (ref "C23") (pin "+") (pinfunction "+_+") (pintype "passive"))
      (node (ref "R5") (pin "2") (pinfunction "2_2") (pintype "passive"))
    )
    (net (code "39") (name "Net-(C24-Pad+)") (class "Default")
      (node (ref "C24") (pin "+") (pinfunction "+_+") (pintype "passive"))
      (node (ref "R6") (pin "2") (pinfunction "2_2") (pintype "passive"))
    )
    (net (code "40") (name "Net-(C31-Pad-)") (class "Default")
      (node (ref "C31") (pin "-") (pinfunction "-_-") (pintype "passive"))
      (node (ref "R25") (pin "1") (pinfunction "1_1") (pintype "passive"))
      (node (ref "R26") (pin "1") (pinfunction "1_1") (pintype "passive"))
    )
    (net (code "41") (name "Net-(C32-Pad-)") (class "Default")
      (node (ref "C32") (pin "-") (pinfunction "-_-") (pintype "passive"))
      (node (ref "R27") (pin "1") (pinfunction "1_1") (pintype "passive"))
      (node (ref "R28") (pin "1") (pinfunction "1_1") (pintype "passive"))
    )
    (net (code "42") (name "Net-(C33-Pad-)") (class "Default")
      (node (ref "C33") (pin "-") (pinfunction "-_-") (pintype "passive"))
      (node (ref "R29") (pin "1") (pinfunction "1_1") (pintype "passive"))
    )
    (net (code "43") (name "Net-(C34-Pad-)") (class "Default")
      (node (ref "C34") (pin "-") (pinfunction "-_-") (pintype "passive"))
      (node (ref "R30") (pin "1") (pinfunction "1_1") (pintype "passive"))
    )
    (net (code "44") (name "Net-(C35-Pad-)") (class "Default")
      (node (ref "C35") (pin "-") (pinfunction "-_-") (pintype "passive"))
      (node (ref "R31") (pin "1") (pinfunction "1_1") (pintype "passive"))
    )
    (net (code "45") (name "Net-(C36-Pad-)") (class "Default")
      (node (ref "C36") (pin "-") (pinfunction "-_-") (pintype "passive"))
      (node (ref "R32") (pin "1") (pinfunction "1_1") (pintype "passive"))
    )
    (net (code "46") (name "Net-(C41-Pad+)") (class "Default")
      (node (ref "C41") (pin "+") (pinfunction "+_+") (pintype "passive"))
      (node (ref "J7") (pin "P$3") (pinfunction "P$3_P$3") (pintype "bidirectional"))
    )
    (net (code "47") (name "Net-(C42-Pad+)") (class "Default")
      (node (ref "C42") (pin "+") (pinfunction "+_+") (pintype "passive"))
      (node (ref "J8") (pin "P$3") (pinfunction "P$3_P$3") (pintype "bidirectional"))
    )
    (net (code "48") (name "Net-(IC1A-+IN)") (class "Default")
      (node (ref "C19") (pin "-") (pinfunction "-_-") (pintype "passive"))
      (node (ref "IC1") (pin "3") (pinfunction "+IN_3") (pintype "input"))
      (node (ref "R7") (pin "2") (pinfunction "2_2") (pintype "passive"))
    )
    (net (code "49") (name "Net-(IC1A--IN)") (class "Default")
      (node (ref "C25") (pin "2") (pinfunction "2_2") (pintype "passive"))
      (node (ref "IC1") (pin "2") (pinfunction "-IN_2") (pintype "input"))
      (node (ref "R13") (pin "2") (pinfunction "2_2") (pintype "passive"))
      (node (ref "R19") (pin "1") (pinfunction "1_1") (pintype "passive"))
    )
    (net (code "50") (name "Net-(IC1A-OUT)") (class "Default")
      (node (ref "C25") (pin "1") (pinfunction "1_1") (pintype "passive"))
      (node (ref "C31") (pin "+") (pinfunction "+_+") (pintype "passive"))
      (node (ref "IC1") (pin "1") (pinfunction "OUT_1") (pintype "output"))
      (node (ref "R19") (pin "2") (pinfunction "2_2") (pintype "passive"))
    )
    (net (code "51") (name "Net-(IC1B-+IN)") (class "Default")
      (node (ref "C20") (pin "-") (pinfunction "-_-") (pintype "passive"))
      (node (ref "IC1") (pin "5") (pinfunction "+IN_5") (pintype "input"))
      (node (ref "R8") (pin "2") (pinfunction "2_2") (pintype "passive"))
    )
    (net (code "52") (name "Net-(IC1B--IN)") (class "Default")
      (node (ref "C26") (pin "2") (pinfunction "2_2") (pintype "passive"))
      (node (ref "IC1") (pin "6") (pinfunction "-IN_6") (pintype "input"))
      (node (ref "R14") (pin "2") (pinfunction "2_2") (pintype "passive"))
      (node (ref "R20") (pin "1") (pinfunction "1_1") (pintype "passive"))
    )
    (net (code "53") (name "Net-(IC1B-OUT)") (class "Default")
      (node (ref "C26") (pin "1") (pinfunction "1_1") (pintype "passive"))
      (node (ref "C32") (pin "+") (pinfunction "+_+") (pintype "passive"))
      (node (ref "IC1") (pin "7") (pinfunction "OUT_7") (pintype "output"))
      (node (ref "R20") (pin "2") (pinfunction "2_2") (pintype "passive"))
    )
    (net (code "54") (name "Net-(IC2A-+IN)") (class "Default")
      (node (ref "C21") (pin "-") (pinfunction "-_-") (pintype "passive"))
      (node (ref "IC2") (pin "3") (pinfunction "+IN_3") (pintype "input"))
      (node (ref "R9") (pin "2") (pinfunction "2_2") (pintype "passive"))
    )
    (net (code "55") (name "Net-(IC2A--IN)") (class "Default")
      (node (ref "C27") (pin "2") (pinfunction "2_2") (pintype "passive"))
      (node (ref "IC2") (pin "2") (pinfunction "-IN_2") (pintype "input"))
      (node (ref "R15") (pin "2") (pinfunction "2_2") (pintype "passive"))
      (node (ref "R21") (pin "1") (pinfunction "1_1") (pintype "passive"))
    )
    (net (code "56") (name "Net-(IC2A-OUT)") (class "Default")
      (node (ref "C27") (pin "1") (pinfunction "1_1") (pintype "passive"))
      (node (ref "C33") (pin "+") (pinfunction "+_+") (pintype "passive"))
      (node (ref "IC2") (pin "1") (pinfunction "OUT_1") (pintype "output"))
      (node (ref "R21") (pin "2") (pinfunction "2_2") (pintype "passive"))
    )
    (net (code "57") (name "Net-(IC2B-+IN)") (class "Default")
      (node (ref "C22") (pin "-") (pinfunction "-_-") (pintype "passive"))
      (node (ref "IC2") (pin "5") (pinfunction "+IN_5") (pintype "input"))
      (node (ref "R10") (pin "2") (pinfunction "2_2") (pintype "passive"))
    )
    (net (code "58") (name "Net-(IC2B--IN)") (class "Default")
      (node (ref "C28") (pin "2") (pinfunction "2_2") (pintype "passive"))
      (node (ref "IC2") (pin "6") (pinfunction "-IN_6") (pintype "input"))
      (node (ref "R16") (pin "2") (pinfunction "2_2") (pintype "passive"))
      (node (ref "R22") (pin "1") (pinfunction "1_1") (pintype "passive"))
    )
    (net (code "59") (name "Net-(IC2B-OUT)") (class "Default")
      (node (ref "C28") (pin "1") (pinfunction "1_1") (pintype "passive"))
      (node (ref "C34") (pin "+") (pinfunction "+_+") (pintype "passive"))
      (node (ref "IC2") (pin "7") (pinfunction "OUT_7") (pintype "output"))
      (node (ref "R22") (pin "2") (pinfunction "2_2") (pintype "passive"))
    )
    (net (code "60") (name "Net-(IC2C-+IN)") (class "Default")
      (node (ref "C23") (pin "-") (pinfunction "-_-") (pintype "passive"))
      (node (ref "IC2") (pin "10") (pinfunction "+IN_10") (pintype "input"))
      (node (ref "R11") (pin "2") (pinfunction "2_2") (pintype "passive"))
    )
    (net (code "61") (name "Net-(IC2C--IN)") (class "Default")
      (node (ref "C29") (pin "2") (pinfunction "2_2") (pintype "passive"))
      (node (ref "IC2") (pin "9") (pinfunction "-IN_9") (pintype "input"))
      (node (ref "R17") (pin "2") (pinfunction "2_2") (pintype "passive"))
      (node (ref "R23") (pin "1") (pinfunction "1_1") (pintype "passive"))
    )
    (net (code "62") (name "Net-(IC2C-OUT)") (class "Default")
      (node (ref "C29") (pin "1") (pinfunction "1_1") (pintype "passive"))
      (node (ref "C35") (pin "+") (pinfunction "+_+") (pintype "passive"))
      (node (ref "IC2") (pin "8") (pinfunction "OUT_8") (pintype "output"))
      (node (ref "R23") (pin "2") (pinfunction "2_2") (pintype "passive"))
    )
    (net (code "63") (name "Net-(IC2D-+IN)") (class "Default")
      (node (ref "C24") (pin "-") (pinfunction "-_-") (pintype "passive"))
      (node (ref "IC2") (pin "12") (pinfunction "+IN_12") (pintype "input"))
      (node (ref "R12") (pin "2") (pinfunction "2_2") (pintype "passive"))
    )
    (net (code "64") (name "Net-(IC2D--IN)") (class "Default")
      (node (ref "C30") (pin "2") (pinfunction "2_2") (pintype "passive"))
      (node (ref "IC2") (pin "13") (pinfunction "-IN_13") (pintype "input"))
      (node (ref "R18") (pin "2") (pinfunction "2_2") (pintype "passive"))
      (node (ref "R24") (pin "1") (pinfunction "1_1") (pintype "passive"))
    )
    (net (code "65") (name "Net-(IC2D-OUT)") (class "Default")
      (node (ref "C30") (pin "1") (pinfunction "1_1") (pintype "passive"))
      (node (ref "C36") (pin "+") (pinfunction "+_+") (pintype "passive"))
      (node (ref "IC2") (pin "14") (pinfunction "OUT_14") (pintype "output"))
      (node (ref "R24") (pin "2") (pinfunction "2_2") (pintype "passive"))
    )
    (net (code "66") (name "Net-(IC3A--IN)") (class "Default")
      (node (ref "C37") (pin "2") (pinfunction "2_2") (pintype "passive"))
      (node (ref "IC3") (pin "2") (pinfunction "-IN_2") (pintype "input"))
      (node (ref "R25") (pin "2") (pinfunction "2_2") (pintype "passive"))
      (node (ref "R27") (pin "2") (pinfunction "2_2") (pintype "passive"))
      (node (ref "R29") (pin "2") (pinfunction "2_2") (pintype "passive"))
      (node (ref "R31") (pin "2") (pinfunction "2_2") (pintype "passive"))
      (node (ref "R33") (pin "2") (pinfunction "2_2") (pintype "passive"))
      (node (ref "R35") (pin "2") (pinfunction "2_2") (pintype "passive"))
      (node (ref "R37") (pin "1") (pinfunction "1_1") (pintype "passive"))
    )
    (net (code "67") (name "Net-(IC3A-OUT)") (class "Default")
      (node (ref "C37") (pin "1") (pinfunction "1_1") (pintype "passive"))
      (node (ref "IC3") (pin "1") (pinfunction "OUT_1") (pintype "output"))
      (node (ref "R37") (pin "2") (pinfunction "2_2") (pintype "passive"))
      (node (ref "R39") (pin "1") (pinfunction "1_1") (pintype "passive"))
    )
    (net (code "68") (name "Net-(IC3B--IN)") (class "Default")
      (node (ref "C39") (pin "2") (pinfunction "2_2") (pintype "passive"))
      (node (ref "IC3") (pin "6") (pinfunction "-IN_6") (pintype "input"))
      (node (ref "R39") (pin "2") (pinfunction "2_2") (pintype "passive"))
      (node (ref "R41") (pin "1") (pinfunction "1_1") (pintype "passive"))
    )
    (net (code "69") (name "Net-(IC3B-OUT)") (class "Default")
      (node (ref "C39") (pin "1") (pinfunction "1_1") (pintype "passive"))
      (node (ref "C43") (pin "-") (pinfunction "-_-") (pintype "passive"))
      (node (ref "IC3") (pin "7") (pinfunction "OUT_7") (pintype "output"))
      (node (ref "R41") (pin "2") (pinfunction "2_2") (pintype "passive"))
    )
    (net (code "70") (name "Net-(IC4A--IN)") (class "Default")
      (node (ref "C38") (pin "2") (pinfunction "2_2") (pintype "passive"))
      (node (ref "IC4") (pin "2") (pinfunction "-IN_2") (pintype "input"))
      (node (ref "R26") (pin "2") (pinfunction "2_2") (pintype "passive"))
      (node (ref "R28") (pin "2") (pinfunction "2_2") (pintype "passive"))
      (node (ref "R30") (pin "2") (pinfunction "2_2") (pintype "passive"))
      (node (ref "R32") (pin "2") (pinfunction "2_2") (pintype "passive"))
      (node (ref "R34") (pin "2") (pinfunction "2_2") (pintype "passive"))
      (node (ref "R36") (pin "2") (pinfunction "2_2") (pintype "passive"))
      (node (ref "R38") (pin "1") (pinfunction "1_1") (pintype "passive"))
    )
    (net (code "71") (name "Net-(IC4A-OUT)") (class "Default")
      (node (ref "C38") (pin "1") (pinfunction "1_1") (pintype "passive"))
      (node (ref "IC4") (pin "1") (pinfunction "OUT_1") (pintype "output"))
      (node (ref "R38") (pin "2") (pinfunction "2_2") (pintype "passive"))
      (node (ref "R40") (pin "1") (pinfunction "1_1") (pintype "passive"))
    )
    (net (code "72") (name "Net-(IC4B--IN)") (class "Default")
      (node (ref "C40") (pin "2") (pinfunction "2_2") (pintype "passive"))
      (node (ref "IC4") (pin "6") (pinfunction "-IN_6") (pintype "input"))
      (node (ref "R40") (pin "2") (pinfunction "2_2") (pintype "passive"))
      (node (ref "R42") (pin "1") (pinfunction "1_1") (pintype "passive"))
    )
    (net (code "73") (name "Net-(IC4B-OUT)") (class "Default")
      (node (ref "C40") (pin "1") (pinfunction "1_1") (pintype "passive"))
      (node (ref "C44") (pin "-") (pinfunction "-_-") (pintype "passive"))
      (node (ref "IC4") (pin "7") (pinfunction "OUT_7") (pintype "output"))
      (node (ref "R42") (pin "2") (pinfunction "2_2") (pintype "passive"))
    )
    (net (code "74") (name "unconnected-(JP1-Pad12)") (class "Default")
      (node (ref "JP1") (pin "12") (pinfunction "12_12") (pintype "passive"))
    )
    (net (code "75") (name "unconnected-(JP1-Pad16)") (class "Default")
      (node (ref "JP1") (pin "16") (pinfunction "16_16") (pintype "passive"))
    )
    (net (code "76") (name "unconnected-(JP3-Pad10)") (class "Default")
      (node (ref "JP3") (pin "10") (pinfunction "10_10") (pintype "passive"))
    )
    (net (code "77") (name "unconnected-(JP3-Pad12)") (class "Default")
      (node (ref "JP3") (pin "12") (pinfunction "12_12") (pintype "passive"))
    )
    (net (code "78") (name "unconnected-(JP3-Pad15)") (class "Default")
      (node (ref "JP3") (pin "15") (pinfunction "15_15") (pintype "passive"))
    )
    (net (code "79") (name "unconnected-(JP3-Pad16)") (class "Default")
      (node (ref "JP3") (pin "16") (pinfunction "16_16") (pintype "passive"))
    )
    (net (code "80") (name "unconnected-(JP4-Pad6)") (class "Default")
      (node (ref "JP4") (pin "6") (pinfunction "6_6") (pintype "passive"))
    )
    (net (code "81") (name "unconnected-(JP4-Pad10)") (class "Default")
      (node (ref "JP4") (pin "10") (pinfunction "10_10") (pintype "passive"))
    )
  )
)
